# SCH_Nucleo____2022-11-04.net
KiCad netlist of a schematic drawn in EasyEDA
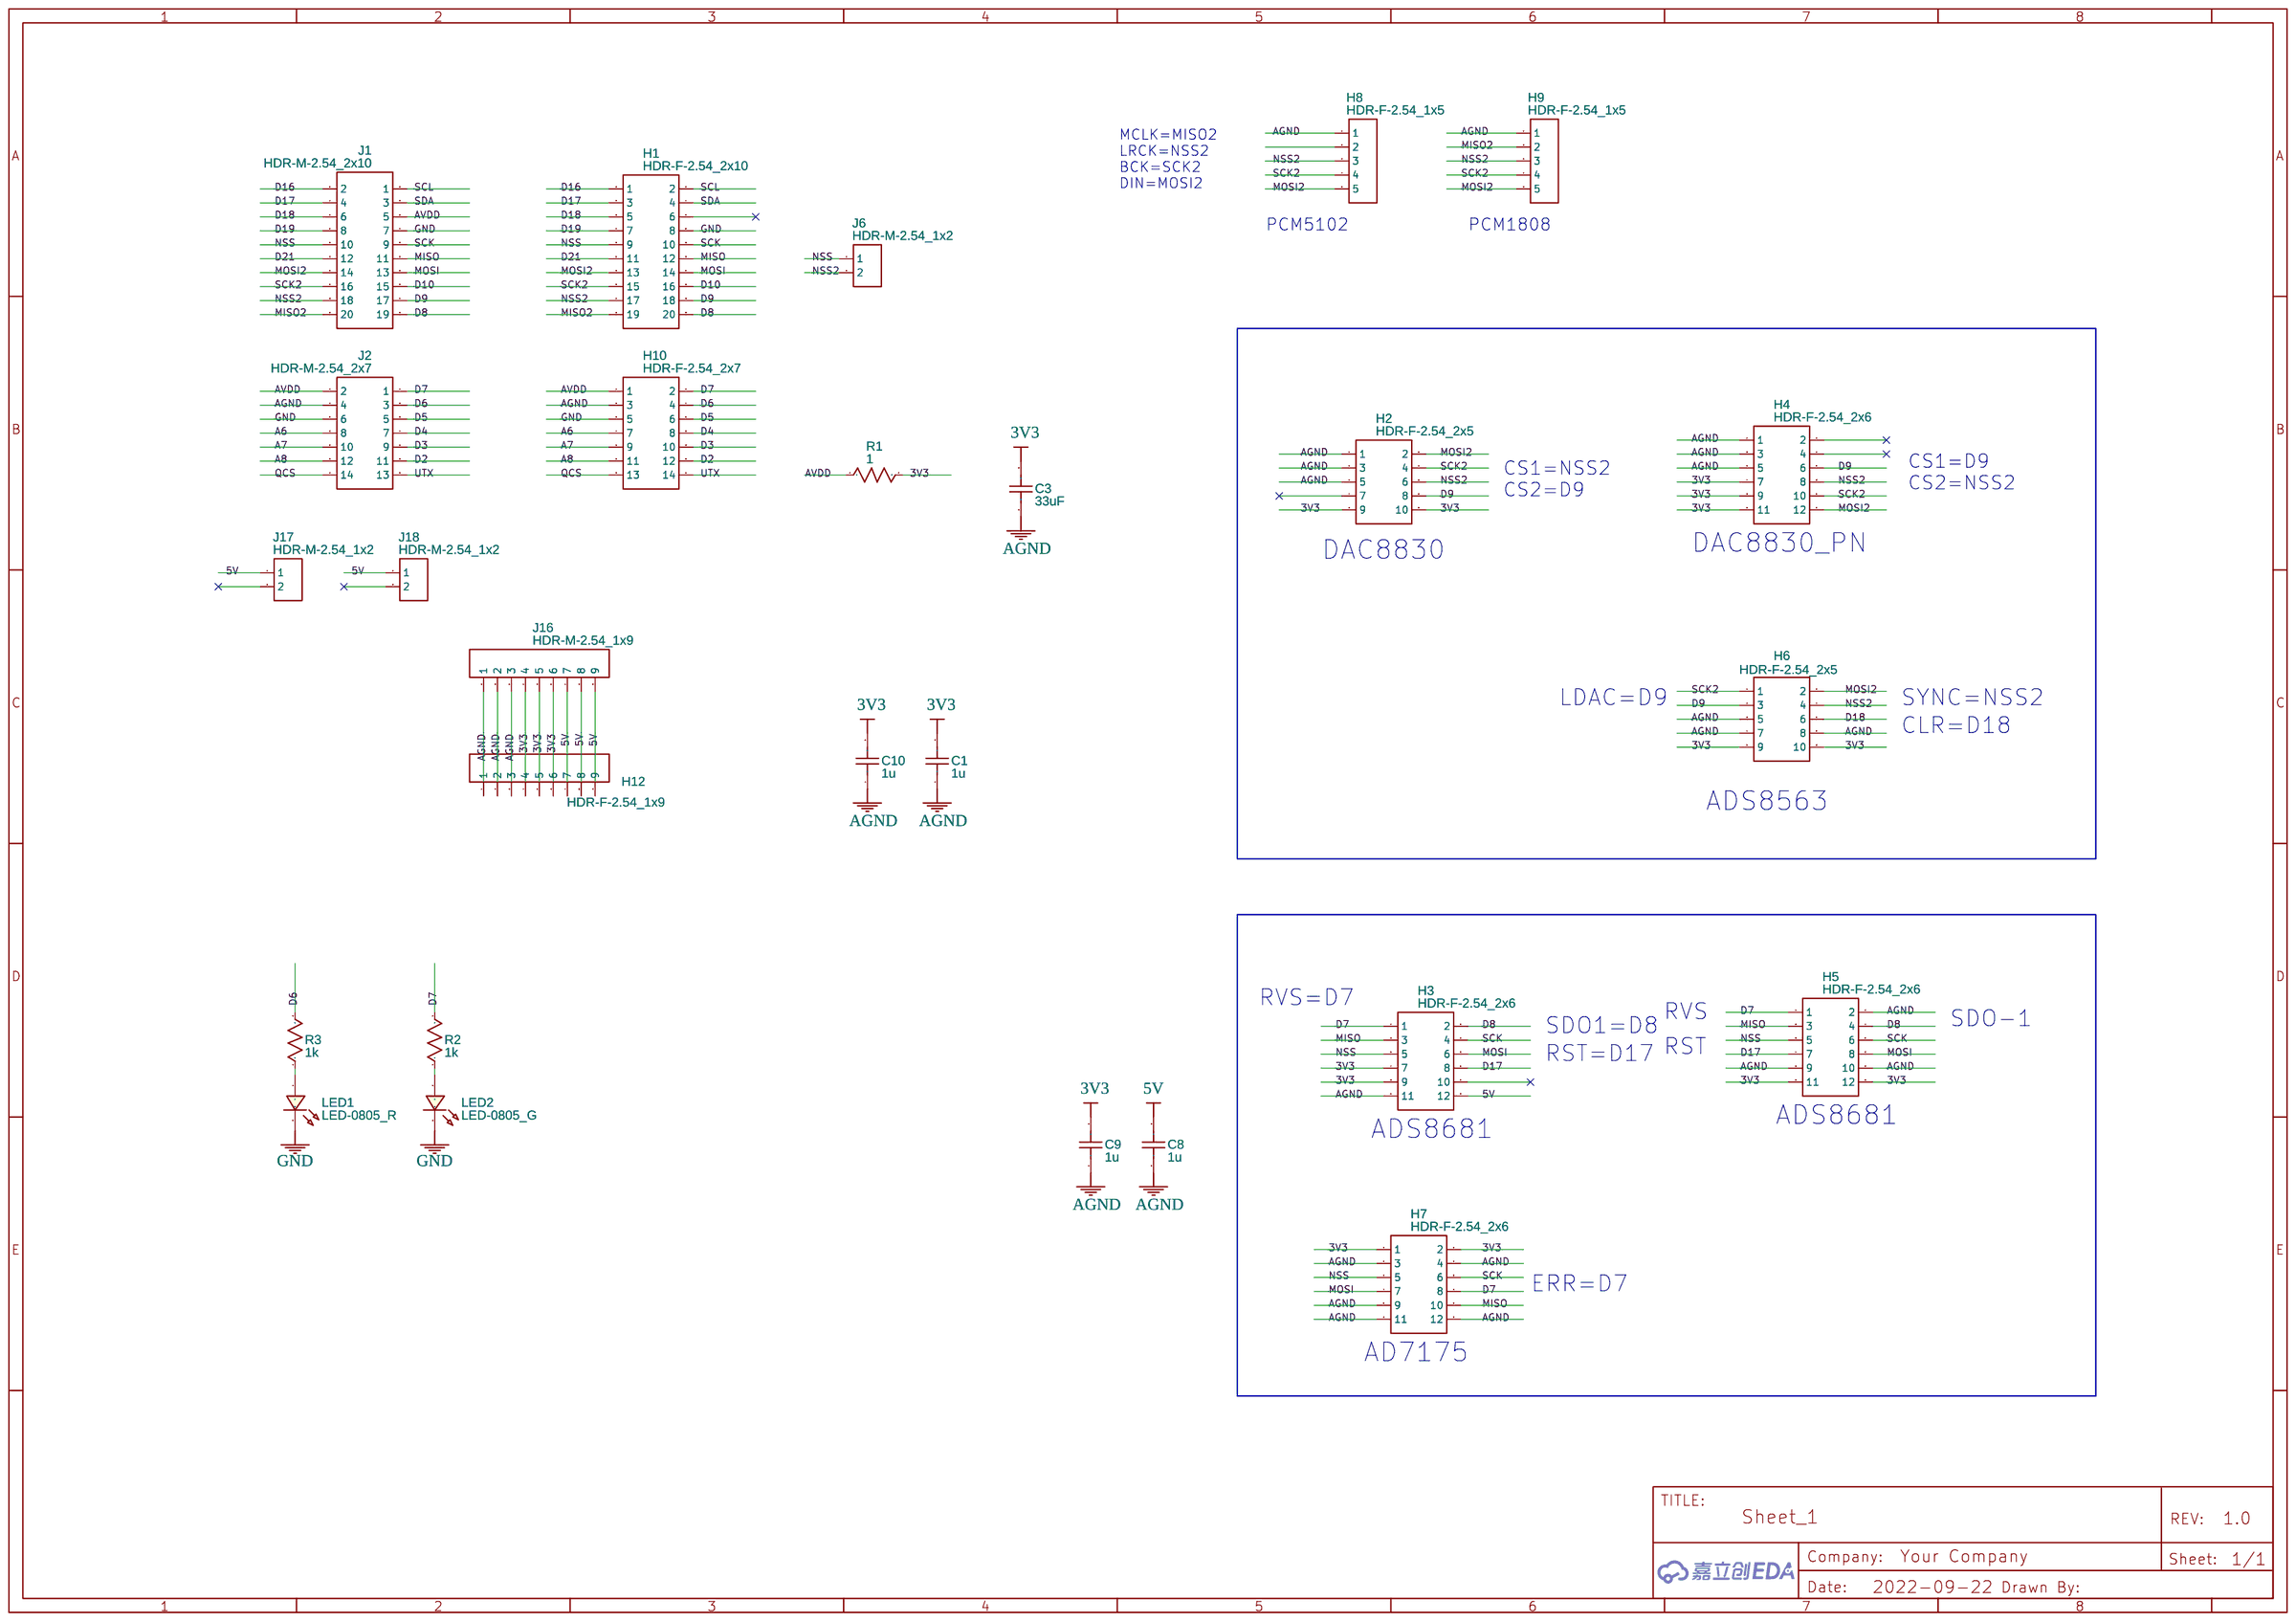
[diagram p0: 连接器]
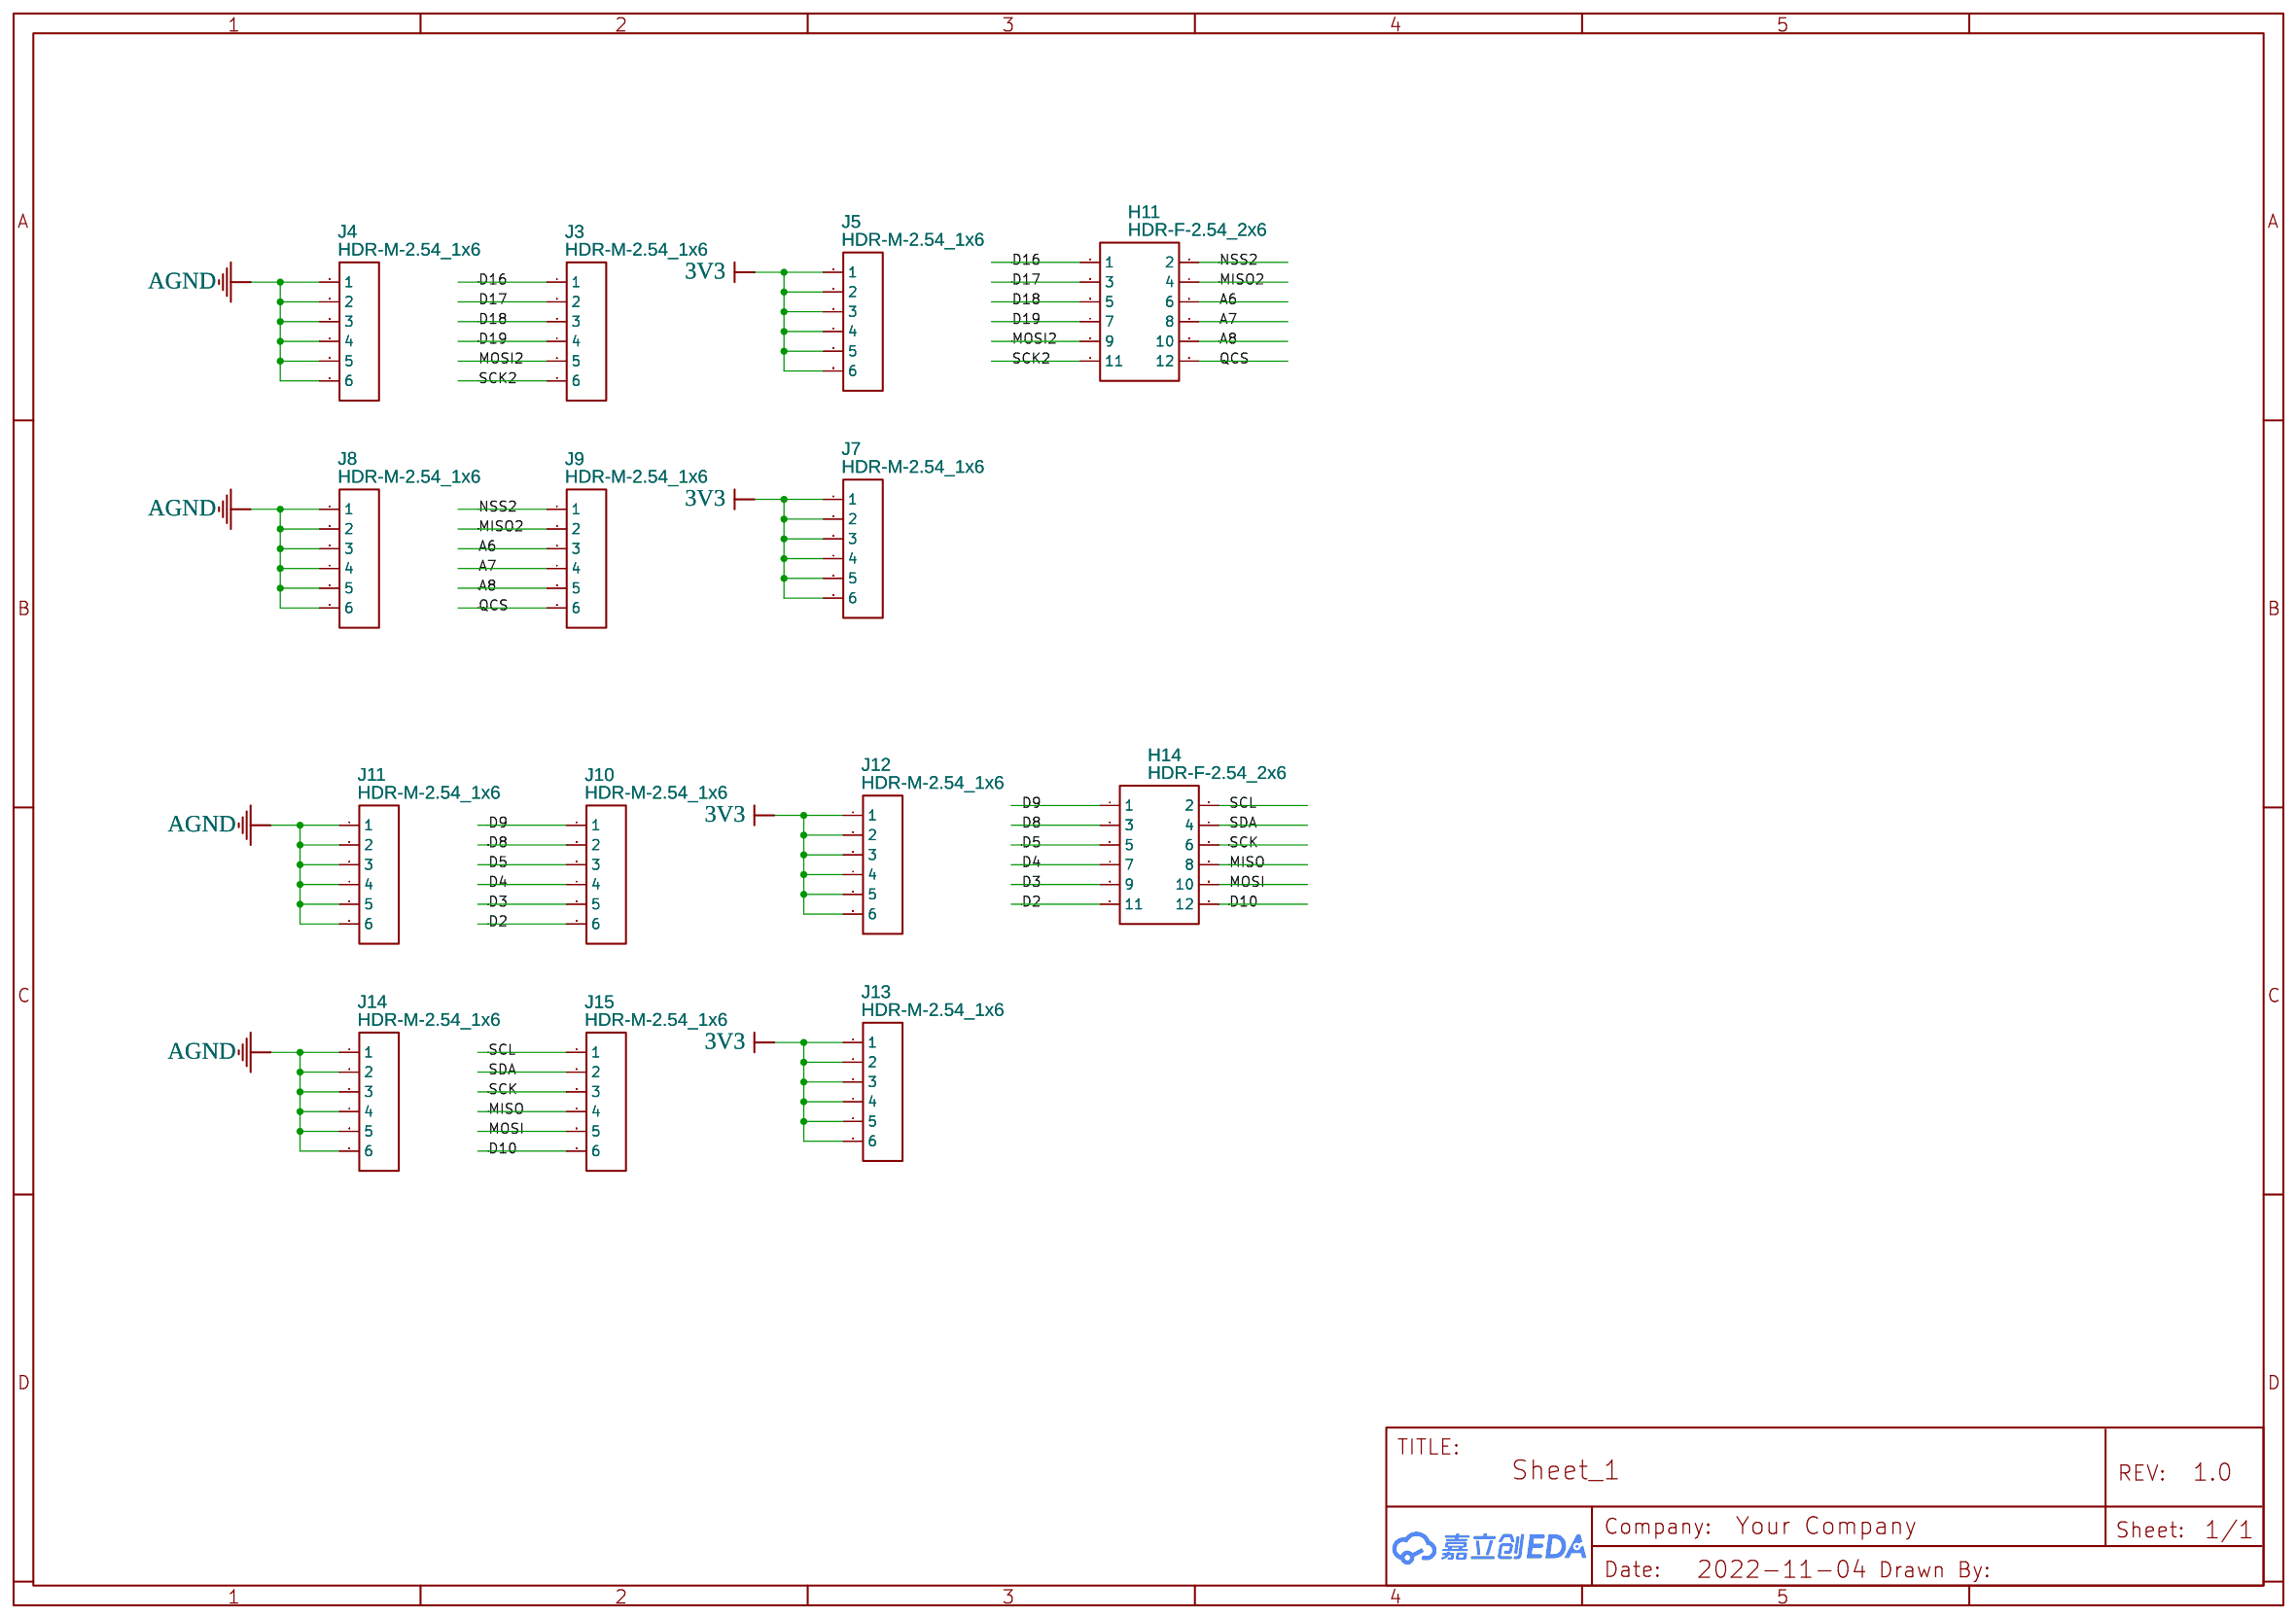
[diagram p1: 连接器2]

(export (version "E")
  (design (tool "Eeschema 10.0.6"))
  (components
    (comp (ref "C1")
      (value "1u")
      (fields
        (field (name "BOM_Manufacturer Part") "0805B105M500NT")
        (field (name "BOM_Supplier Part") "C2913555")
      )
      (libsource (lib "") (part "C_0805_US"))
    )
    (comp (ref "C3")
      (value "33uF")
      (fields
        (field (name "BOM_Manufacturer Part") "C3225X5R0J336MT0A0N")
        (field (name "BOM_Supplier Part") "C695362")
      )
      (libsource (lib "") (part "C3225X5R0J336MT0A0N"))
    )
    (comp (ref "C8")
      (value "1u")
      (fields
        (field (name "BOM_Manufacturer Part") "0805B105M500NT")
        (field (name "BOM_Supplier Part") "C2913555")
      )
      (libsource (lib "") (part "C_0805_US"))
    )
    (comp (ref "C9")
      (value "1u")
      (fields
        (field (name "BOM_Manufacturer Part") "0805B105M500NT")
        (field (name "BOM_Supplier Part") "C2913555")
      )
      (libsource (lib "") (part "C_0805_US"))
    )
    (comp (ref "C10")
      (value "1u")
      (fields
        (field (name "BOM_Manufacturer Part") "0805B105M500NT")
        (field (name "BOM_Supplier Part") "C2913555")
      )
      (libsource (lib "") (part "C_0805_US"))
    )
    (comp (ref "H1")
      (value "HDR-F-2.54_2x10")
      (fields (field (name "BOM_Supplier Part") "C30867"))
      (libsource (lib "") (part "HDR-F-2.54_2x10"))
    )
    (comp (ref "H2")
      (value "HDR-F-2.54_2x5")
      (fields (field (name "BOM_Supplier Part") "C30419"))
      (libsource (lib "") (part "HDR-F-2.54_2x5"))
    )
    (comp (ref "H3")
      (value "HDR-F-2.54_2x6")
      (fields (field (name "BOM_Supplier Part") "C36191"))
      (libsource (lib "") (part "HDR-F-2.54_2x6"))
    )
    (comp (ref "H4")
      (value "HDR-F-2.54_2x6")
      (fields (field (name "BOM_Supplier Part") "C36191"))
      (libsource (lib "") (part "HDR-F-2.54_2x6"))
    )
    (comp (ref "H5")
      (value "HDR-F-2.54_2x6")
      (fields (field (name "BOM_Supplier Part") "C36191"))
      (libsource (lib "") (part "HDR-F-2.54_2x6"))
    )
    (comp (ref "H6")
      (value "HDR-F-2.54_2x5")
      (fields (field (name "BOM_Supplier Part") "C30419"))
      (libsource (lib "") (part "HDR-F-2.54_2x5"))
    )
    (comp (ref "H7")
      (value "HDR-F-2.54_2x6")
      (fields (field (name "BOM_Supplier Part") "C36191"))
      (libsource (lib "") (part "HDR-F-2.54_2x6"))
    )
    (comp (ref "H8")
      (value "HDR-F-2.54_1x5")
      (fields (field (name "BOM_Supplier Part") "C50950"))
      (libsource (lib "") (part "HDR-F-2.54_1x5"))
    )
    (comp (ref "H9")
      (value "HDR-F-2.54_1x5")
      (fields (field (name "BOM_Supplier Part") "C50950"))
      (libsource (lib "") (part "HDR-F-2.54_1x5"))
    )
    (comp (ref "H10")
      (value "HDR-F-2.54_2x7")
      (fields (field (name "BOM_Supplier Part") "C38844"))
      (libsource (lib "") (part "HDR-F-2.54_2x7"))
    )
    (comp (ref "H12")
      (value "HDR-F-2.54_1x9")
      (fields (field (name "BOM_Supplier Part") "C124417"))
      (libsource (lib "") (part "HDR-F-2.54_1x9"))
    )
    (comp (ref "J1")
      (value "HDR-M-2.54_2x10")
      (fields (field (name "BOM_Supplier Part") "C124359"))
      (libsource (lib "") (part "HDR-M-2.54_2x10"))
    )
    (comp (ref "J2")
      (value "HDR-M-2.54_2x7")
      (fields (field (name "BOM_Supplier Part") "C71397"))
      (libsource (lib "") (part "HDR-M-2.54_2x7"))
    )
    (comp (ref "J6")
      (value "HDR-M-2.54_1x2")
      (fields (field (name "BOM_Supplier Part") "C124375"))
      (libsource (lib "") (part "HDR-M-2.54_1x2"))
    )
    (comp (ref "J16")
      (value "HDR-M-2.54_1x9")
      (fields (field (name "BOM_Supplier Part") "C225484"))
      (libsource (lib "") (part "HDR-M-2.54_1x9"))
    )
    (comp (ref "J17")
      (value "HDR-M-2.54_1x2")
      (fields (field (name "BOM_Supplier Part") "C124375"))
      (libsource (lib "") (part "HDR-M-2.54_1x2"))
    )
    (comp (ref "J18")
      (value "HDR-M-2.54_1x2")
      (fields (field (name "BOM_Supplier Part") "C124375"))
      (libsource (lib "") (part "HDR-M-2.54_1x2"))
    )
    (comp (ref "LED1")
      (value "LED-0805_R")
      (fields
        (field (name "BOM_Manufacturer Part") "17-21SURC/S530-A3/TR8")
        (field (name "BOM_Supplier Part") "C72037")
      )
      (libsource (lib "") (part "LED-0805_R"))
    )
    (comp (ref "LED2")
      (value "LED-0805_G")
      (fields (field (name "BOM_Manufacturer Part") "NCD0805G1") (field (name "BOM_Supplier Part") "C84260"))
      (libsource (lib "") (part "LED-0805_G"))
    )
    (comp (ref "R1") (value "1") (libsource (lib "") (part "R_0805_US_1")))
    (comp (ref "R2")
      (value "1k")
      (fields
        (field (name "BOM_Manufacturer Part") "TC0525F1001T5E")
        (field (name "BOM_Supplier Part") "C75781")
      )
      (libsource (lib "") (part "R_0805_US"))
    )
    (comp (ref "R3")
      (value "1k")
      (fields
        (field (name "BOM_Manufacturer Part") "TC0525F1001T5E")
        (field (name "BOM_Supplier Part") "C75781")
      )
      (libsource (lib "") (part "R_0805_US"))
    )
    (comp (ref "H11")
      (value "HDR-F-2.54_2x6")
      (fields (field (name "BOM_Supplier Part") "C36191"))
      (libsource (lib "") (part "HDR-F-2.54_2x6"))
    )
    (comp (ref "H14")
      (value "HDR-F-2.54_2x6")
      (fields (field (name "BOM_Supplier Part") "C36191"))
      (libsource (lib "") (part "HDR-F-2.54_2x6"))
    )
    (comp (ref "J3")
      (value "HDR-M-2.54_1x6")
      (fields (field (name "BOM_Supplier Part") "C190819"))
      (libsource (lib "") (part "HDR-M-2.54_1x6"))
    )
    (comp (ref "J4")
      (value "HDR-M-2.54_1x6")
      (fields (field (name "BOM_Supplier Part") "C190819"))
      (libsource (lib "") (part "HDR-M-2.54_1x6"))
    )
    (comp (ref "J5")
      (value "HDR-M-2.54_1x6")
      (fields (field (name "BOM_Supplier Part") "C190819"))
      (libsource (lib "") (part "HDR-M-2.54_1x6"))
    )
    (comp (ref "J7")
      (value "HDR-M-2.54_1x6")
      (fields (field (name "BOM_Supplier Part") "C190819"))
      (libsource (lib "") (part "HDR-M-2.54_1x6"))
    )
    (comp (ref "J8")
      (value "HDR-M-2.54_1x6")
      (fields (field (name "BOM_Supplier Part") "C190819"))
      (libsource (lib "") (part "HDR-M-2.54_1x6"))
    )
    (comp (ref "J9")
      (value "HDR-M-2.54_1x6")
      (fields (field (name "BOM_Supplier Part") "C190819"))
      (libsource (lib "") (part "HDR-M-2.54_1x6"))
    )
    (comp (ref "J10")
      (value "HDR-M-2.54_1x6")
      (fields (field (name "BOM_Supplier Part") "C190819"))
      (libsource (lib "") (part "HDR-M-2.54_1x6"))
    )
    (comp (ref "J11")
      (value "HDR-M-2.54_1x6")
      (fields (field (name "BOM_Supplier Part") "C190819"))
      (libsource (lib "") (part "HDR-M-2.54_1x6"))
    )
    (comp (ref "J12")
      (value "HDR-M-2.54_1x6")
      (fields (field (name "BOM_Supplier Part") "C190819"))
      (libsource (lib "") (part "HDR-M-2.54_1x6"))
    )
    (comp (ref "J13")
      (value "HDR-M-2.54_1x6")
      (fields (field (name "BOM_Supplier Part") "C190819"))
      (libsource (lib "") (part "HDR-M-2.54_1x6"))
    )
    (comp (ref "J14")
      (value "HDR-M-2.54_1x6")
      (fields (field (name "BOM_Supplier Part") "C190819"))
      (libsource (lib "") (part "HDR-M-2.54_1x6"))
    )
    (comp (ref "J15")
      (value "HDR-M-2.54_1x6")
      (fields (field (name "BOM_Supplier Part") "C190819"))
      (libsource (lib "") (part "HDR-M-2.54_1x6"))
    )
  )
  (nets
    (net (code "1") (name "3V3") (class "Default")
      (node (ref "C1") (pin "2") (pinfunction "2_2") (pintype "unspecified"))
      (node (ref "C10") (pin "2") (pinfunction "2_2") (pintype "unspecified"))
      (node (ref "C3") (pin "2") (pinfunction "2_2") (pintype "unspecified"))
      (node (ref "C9") (pin "2") (pinfunction "2_2") (pintype "unspecified"))
      (node (ref "H12") (pin "4") (pinfunction "4_4") (pintype "unspecified"))
      (node (ref "H12") (pin "5") (pinfunction "5_5") (pintype "unspecified"))
      (node (ref "H12") (pin "6") (pinfunction "6_6") (pintype "unspecified"))
      (node (ref "H2") (pin "10") (pinfunction "10_10") (pintype "unspecified"))
      (node (ref "H2") (pin "9") (pinfunction "9_9") (pintype "unspecified"))
      (node (ref "H3") (pin "7") (pinfunction "7_7") (pintype "input"))
      (node (ref "H3") (pin "9") (pinfunction "9_9") (pintype "input"))
      (node (ref "H4") (pin "11") (pinfunction "11_11") (pintype "input"))
      (node (ref "H4") (pin "7") (pinfunction "7_7") (pintype "input"))
      (node (ref "H4") (pin "9") (pinfunction "9_9") (pintype "input"))
      (node (ref "H5") (pin "11") (pinfunction "11_11") (pintype "input"))
      (node (ref "H5") (pin "12") (pinfunction "12_12") (pintype "input"))
      (node (ref "H6") (pin "10") (pinfunction "10_10") (pintype "unspecified"))
      (node (ref "H6") (pin "9") (pinfunction "9_9") (pintype "unspecified"))
      (node (ref "H7") (pin "1") (pinfunction "1_1") (pintype "input"))
      (node (ref "H7") (pin "2") (pinfunction "2_2") (pintype "input"))
      (node (ref "J12") (pin "1") (pinfunction "1_1") (pintype "input"))
      (node (ref "J12") (pin "2") (pinfunction "2_2") (pintype "input"))
      (node (ref "J12") (pin "3") (pinfunction "3_3") (pintype "input"))
      (node (ref "J12") (pin "4") (pinfunction "4_4") (pintype "input"))
      (node (ref "J12") (pin "5") (pinfunction "5_5") (pintype "input"))
      (node (ref "J12") (pin "6") (pinfunction "6_6") (pintype "input"))
      (node (ref "J13") (pin "1") (pinfunction "1_1") (pintype "input"))
      (node (ref "J13") (pin "2") (pinfunction "2_2") (pintype "input"))
      (node (ref "J13") (pin "3") (pinfunction "3_3") (pintype "input"))
      (node (ref "J13") (pin "4") (pinfunction "4_4") (pintype "input"))
      (node (ref "J13") (pin "5") (pinfunction "5_5") (pintype "input"))
      (node (ref "J13") (pin "6") (pinfunction "6_6") (pintype "input"))
      (node (ref "J16") (pin "4") (pinfunction "4_4") (pintype "unspecified"))
      (node (ref "J16") (pin "5") (pinfunction "5_5") (pintype "unspecified"))
      (node (ref "J16") (pin "6") (pinfunction "6_6") (pintype "unspecified"))
      (node (ref "J5") (pin "1") (pinfunction "1_1") (pintype "input"))
      (node (ref "J5") (pin "2") (pinfunction "2_2") (pintype "input"))
      (node (ref "J5") (pin "3") (pinfunction "3_3") (pintype "input"))
      (node (ref "J5") (pin "4") (pinfunction "4_4") (pintype "input"))
      (node (ref "J5") (pin "5") (pinfunction "5_5") (pintype "input"))
      (node (ref "J5") (pin "6") (pinfunction "6_6") (pintype "input"))
      (node (ref "J7") (pin "1") (pinfunction "1_1") (pintype "input"))
      (node (ref "J7") (pin "2") (pinfunction "2_2") (pintype "input"))
      (node (ref "J7") (pin "3") (pinfunction "3_3") (pintype "input"))
      (node (ref "J7") (pin "4") (pinfunction "4_4") (pintype "input"))
      (node (ref "J7") (pin "5") (pinfunction "5_5") (pintype "input"))
      (node (ref "J7") (pin "6") (pinfunction "6_6") (pintype "input"))
      (node (ref "R1") (pin "2") (pinfunction "2_2") (pintype "unspecified"))
    )
    (net (code "2") (name "5V") (class "Default")
      (node (ref "C8") (pin "2") (pinfunction "2_2") (pintype "unspecified"))
      (node (ref "H12") (pin "7") (pinfunction "7_7") (pintype "unspecified"))
      (node (ref "H12") (pin "8") (pinfunction "8_8") (pintype "unspecified"))
      (node (ref "H12") (pin "9") (pinfunction "9_9") (pintype "unspecified"))
      (node (ref "H3") (pin "12") (pinfunction "12_12") (pintype "input"))
      (node (ref "J16") (pin "7") (pinfunction "7_7") (pintype "unspecified"))
      (node (ref "J16") (pin "8") (pinfunction "8_8") (pintype "unspecified"))
      (node (ref "J16") (pin "9") (pinfunction "9_9") (pintype "unspecified"))
      (node (ref "J17") (pin "1") (pinfunction "1_1") (pintype "unspecified"))
      (node (ref "J18") (pin "1") (pinfunction "1_1") (pintype "unspecified"))
    )
    (net (code "3") (name "A6") (class "Default")
      (node (ref "H10") (pin "7") (pinfunction "7_7") (pintype "input"))
      (node (ref "H11") (pin "6") (pinfunction "6_6") (pintype "input"))
      (node (ref "J2") (pin "8") (pinfunction "8_8") (pintype "input"))
      (node (ref "J9") (pin "3") (pinfunction "3_3") (pintype "input"))
    )
    (net (code "4") (name "A7") (class "Default")
      (node (ref "H10") (pin "9") (pinfunction "9_9") (pintype "input"))
      (node (ref "H11") (pin "8") (pinfunction "8_8") (pintype "input"))
      (node (ref "J2") (pin "10") (pinfunction "10_10") (pintype "input"))
      (node (ref "J9") (pin "4") (pinfunction "4_4") (pintype "input"))
    )
    (net (code "5") (name "A8") (class "Default")
      (node (ref "H10") (pin "11") (pinfunction "11_11") (pintype "input"))
      (node (ref "H11") (pin "10") (pinfunction "10_10") (pintype "input"))
      (node (ref "J2") (pin "12") (pinfunction "12_12") (pintype "input"))
      (node (ref "J9") (pin "5") (pinfunction "5_5") (pintype "input"))
    )
    (net (code "6") (name "AGND") (class "Default")
      (node (ref "C1") (pin "1") (pinfunction "1_1") (pintype "unspecified"))
      (node (ref "C10") (pin "1") (pinfunction "1_1") (pintype "unspecified"))
      (node (ref "C3") (pin "1") (pinfunction "1_1") (pintype "unspecified"))
      (node (ref "C8") (pin "1") (pinfunction "1_1") (pintype "unspecified"))
      (node (ref "C9") (pin "1") (pinfunction "1_1") (pintype "unspecified"))
      (node (ref "H10") (pin "3") (pinfunction "3_3") (pintype "input"))
      (node (ref "H12") (pin "1") (pinfunction "1_1") (pintype "unspecified"))
      (node (ref "H12") (pin "2") (pinfunction "2_2") (pintype "unspecified"))
      (node (ref "H12") (pin "3") (pinfunction "3_3") (pintype "unspecified"))
      (node (ref "H2") (pin "1") (pinfunction "1_1") (pintype "unspecified"))
      (node (ref "H2") (pin "3") (pinfunction "3_3") (pintype "unspecified"))
      (node (ref "H2") (pin "5") (pinfunction "5_5") (pintype "unspecified"))
      (node (ref "H3") (pin "11") (pinfunction "11_11") (pintype "input"))
      (node (ref "H4") (pin "1") (pinfunction "1_1") (pintype "input"))
      (node (ref "H4") (pin "3") (pinfunction "3_3") (pintype "input"))
      (node (ref "H4") (pin "5") (pinfunction "5_5") (pintype "input"))
      (node (ref "H5") (pin "10") (pinfunction "10_10") (pintype "input"))
      (node (ref "H5") (pin "2") (pinfunction "2_2") (pintype "input"))
      (node (ref "H5") (pin "9") (pinfunction "9_9") (pintype "input"))
      (node (ref "H6") (pin "5") (pinfunction "5_5") (pintype "unspecified"))
      (node (ref "H6") (pin "7") (pinfunction "7_7") (pintype "unspecified"))
      (node (ref "H6") (pin "8") (pinfunction "8_8") (pintype "unspecified"))
      (node (ref "H7") (pin "11") (pinfunction "11_11") (pintype "input"))
      (node (ref "H7") (pin "12") (pinfunction "12_12") (pintype "input"))
      (node (ref "H7") (pin "3") (pinfunction "3_3") (pintype "input"))
      (node (ref "H7") (pin "4") (pinfunction "4_4") (pintype "input"))
      (node (ref "H7") (pin "9") (pinfunction "9_9") (pintype "input"))
      (node (ref "H8") (pin "1") (pinfunction "1_1") (pintype "unspecified"))
      (node (ref "H9") (pin "1") (pinfunction "1_1") (pintype "unspecified"))
      (node (ref "J11") (pin "1") (pinfunction "1_1") (pintype "input"))
      (node (ref "J11") (pin "2") (pinfunction "2_2") (pintype "input"))
      (node (ref "J11") (pin "3") (pinfunction "3_3") (pintype "input"))
      (node (ref "J11") (pin "4") (pinfunction "4_4") (pintype "input"))
      (node (ref "J11") (pin "5") (pinfunction "5_5") (pintype "input"))
      (node (ref "J11") (pin "6") (pinfunction "6_6") (pintype "input"))
      (node (ref "J14") (pin "1") (pinfunction "1_1") (pintype "input"))
      (node (ref "J14") (pin "2") (pinfunction "2_2") (pintype "input"))
      (node (ref "J14") (pin "3") (pinfunction "3_3") (pintype "input"))
      (node (ref "J14") (pin "4") (pinfunction "4_4") (pintype "input"))
      (node (ref "J14") (pin "5") (pinfunction "5_5") (pintype "input"))
      (node (ref "J14") (pin "6") (pinfunction "6_6") (pintype "input"))
      (node (ref "J16") (pin "1") (pinfunction "1_1") (pintype "unspecified"))
      (node (ref "J16") (pin "2") (pinfunction "2_2") (pintype "unspecified"))
      (node (ref "J16") (pin "3") (pinfunction "3_3") (pintype "unspecified"))
      (node (ref "J2") (pin "4") (pinfunction "4_4") (pintype "input"))
      (node (ref "J4") (pin "1") (pinfunction "1_1") (pintype "input"))
      (node (ref "J4") (pin "2") (pinfunction "2_2") (pintype "input"))
      (node (ref "J4") (pin "3") (pinfunction "3_3") (pintype "input"))
      (node (ref "J4") (pin "4") (pinfunction "4_4") (pintype "input"))
      (node (ref "J4") (pin "5") (pinfunction "5_5") (pintype "input"))
      (node (ref "J4") (pin "6") (pinfunction "6_6") (pintype "input"))
      (node (ref "J8") (pin "1") (pinfunction "1_1") (pintype "input"))
      (node (ref "J8") (pin "2") (pinfunction "2_2") (pintype "input"))
      (node (ref "J8") (pin "3") (pinfunction "3_3") (pintype "input"))
      (node (ref "J8") (pin "4") (pinfunction "4_4") (pintype "input"))
      (node (ref "J8") (pin "5") (pinfunction "5_5") (pintype "input"))
      (node (ref "J8") (pin "6") (pinfunction "6_6") (pintype "input"))
    )
    (net (code "7") (name "AVDD") (class "Default")
      (node (ref "H10") (pin "1") (pinfunction "1_1") (pintype "input"))
      (node (ref "J1") (pin "5") (pinfunction "5_5") (pintype "unspecified"))
      (node (ref "J2") (pin "2") (pinfunction "2_2") (pintype "input"))
      (node (ref "R1") (pin "1") (pinfunction "1_1") (pintype "unspecified"))
    )
    (net (code "8") (name "D2") (class "Default")
      (node (ref "H10") (pin "12") (pinfunction "12_12") (pintype "input"))
      (node (ref "H14") (pin "11") (pinfunction "11_11") (pintype "input"))
      (node (ref "J10") (pin "6") (pinfunction "6_6") (pintype "input"))
      (node (ref "J2") (pin "11") (pinfunction "11_11") (pintype "input"))
    )
    (net (code "9") (name "D3") (class "Default")
      (node (ref "H10") (pin "10") (pinfunction "10_10") (pintype "input"))
      (node (ref "H14") (pin "9") (pinfunction "9_9") (pintype "input"))
      (node (ref "J10") (pin "5") (pinfunction "5_5") (pintype "input"))
      (node (ref "J2") (pin "9") (pinfunction "9_9") (pintype "input"))
    )
    (net (code "10") (name "D4") (class "Default")
      (node (ref "H10") (pin "8") (pinfunction "8_8") (pintype "input"))
      (node (ref "H14") (pin "7") (pinfunction "7_7") (pintype "input"))
      (node (ref "J10") (pin "4") (pinfunction "4_4") (pintype "input"))
      (node (ref "J2") (pin "7") (pinfunction "7_7") (pintype "input"))
    )
    (net (code "11") (name "D5") (class "Default")
      (node (ref "H10") (pin "6") (pinfunction "6_6") (pintype "input"))
      (node (ref "H14") (pin "5") (pinfunction "5_5") (pintype "input"))
      (node (ref "J10") (pin "3") (pinfunction "3_3") (pintype "input"))
      (node (ref "J2") (pin "5") (pinfunction "5_5") (pintype "input"))
    )
    (net (code "12") (name "D6") (class "Default")
      (node (ref "H10") (pin "4") (pinfunction "4_4") (pintype "input"))
      (node (ref "J2") (pin "3") (pinfunction "3_3") (pintype "input"))
      (node (ref "R3") (pin "2") (pinfunction "2_2") (pintype "unspecified"))
    )
    (net (code "13") (name "D7") (class "Default")
      (node (ref "H10") (pin "2") (pinfunction "2_2") (pintype "input"))
      (node (ref "H3") (pin "1") (pinfunction "1_1") (pintype "input"))
      (node (ref "H5") (pin "1") (pinfunction "1_1") (pintype "input"))
      (node (ref "H7") (pin "8") (pinfunction "8_8") (pintype "input"))
      (node (ref "J2") (pin "1") (pinfunction "1_1") (pintype "input"))
      (node (ref "R2") (pin "2") (pinfunction "2_2") (pintype "unspecified"))
    )
    (net (code "14") (name "D8") (class "Default")
      (node (ref "H1") (pin "20") (pinfunction "20_20") (pintype "input"))
      (node (ref "H14") (pin "3") (pinfunction "3_3") (pintype "input"))
      (node (ref "H3") (pin "2") (pinfunction "2_2") (pintype "input"))
      (node (ref "H5") (pin "4") (pinfunction "4_4") (pintype "input"))
      (node (ref "J1") (pin "19") (pinfunction "19_19") (pintype "unspecified"))
      (node (ref "J10") (pin "2") (pinfunction "2_2") (pintype "input"))
    )
    (net (code "15") (name "D9") (class "Default")
      (node (ref "H1") (pin "18") (pinfunction "18_18") (pintype "input"))
      (node (ref "H14") (pin "1") (pinfunction "1_1") (pintype "input"))
      (node (ref "H2") (pin "8") (pinfunction "8_8") (pintype "unspecified"))
      (node (ref "H4") (pin "6") (pinfunction "6_6") (pintype "input"))
      (node (ref "H6") (pin "3") (pinfunction "3_3") (pintype "unspecified"))
      (node (ref "J1") (pin "17") (pinfunction "17_17") (pintype "unspecified"))
      (node (ref "J10") (pin "1") (pinfunction "1_1") (pintype "input"))
    )
    (net (code "16") (name "D10") (class "Default")
      (node (ref "H1") (pin "16") (pinfunction "16_16") (pintype "input"))
      (node (ref "H14") (pin "12") (pinfunction "12_12") (pintype "input"))
      (node (ref "J1") (pin "15") (pinfunction "15_15") (pintype "unspecified"))
      (node (ref "J15") (pin "6") (pinfunction "6_6") (pintype "input"))
    )
    (net (code "17") (name "D16") (class "Default")
      (node (ref "H1") (pin "1") (pinfunction "1_1") (pintype "input"))
      (node (ref "H11") (pin "1") (pinfunction "1_1") (pintype "input"))
      (node (ref "J1") (pin "2") (pinfunction "2_2") (pintype "unspecified"))
      (node (ref "J3") (pin "1") (pinfunction "1_1") (pintype "input"))
    )
    (net (code "18") (name "D17") (class "Default")
      (node (ref "H1") (pin "3") (pinfunction "3_3") (pintype "input"))
      (node (ref "H11") (pin "3") (pinfunction "3_3") (pintype "input"))
      (node (ref "H3") (pin "8") (pinfunction "8_8") (pintype "input"))
      (node (ref "H5") (pin "7") (pinfunction "7_7") (pintype "input"))
      (node (ref "J1") (pin "4") (pinfunction "4_4") (pintype "unspecified"))
      (node (ref "J3") (pin "2") (pinfunction "2_2") (pintype "input"))
    )
    (net (code "19") (name "D18") (class "Default")
      (node (ref "H1") (pin "5") (pinfunction "5_5") (pintype "input"))
      (node (ref "H11") (pin "5") (pinfunction "5_5") (pintype "input"))
      (node (ref "H6") (pin "6") (pinfunction "6_6") (pintype "unspecified"))
      (node (ref "J1") (pin "6") (pinfunction "6_6") (pintype "unspecified"))
      (node (ref "J3") (pin "3") (pinfunction "3_3") (pintype "input"))
    )
    (net (code "20") (name "D19") (class "Default")
      (node (ref "H1") (pin "7") (pinfunction "7_7") (pintype "input"))
      (node (ref "H11") (pin "7") (pinfunction "7_7") (pintype "input"))
      (node (ref "J1") (pin "8") (pinfunction "8_8") (pintype "unspecified"))
      (node (ref "J3") (pin "4") (pinfunction "4_4") (pintype "input"))
    )
    (net (code "21") (name "D21") (class "Default")
      (node (ref "H1") (pin "11") (pinfunction "11_11") (pintype "input"))
      (node (ref "J1") (pin "12") (pinfunction "12_12") (pintype "unspecified"))
    )
    (net (code "22") (name "GND") (class "Default")
      (node (ref "H1") (pin "8") (pinfunction "8_8") (pintype "input"))
      (node (ref "H10") (pin "5") (pinfunction "5_5") (pintype "input"))
      (node (ref "J1") (pin "7") (pinfunction "7_7") (pintype "unspecified"))
      (node (ref "J2") (pin "6") (pinfunction "6_6") (pintype "input"))
      (node (ref "LED1") (pin "2") (pinfunction "2_2") (pintype "unspecified"))
      (node (ref "LED2") (pin "2") (pinfunction "2_2") (pintype "unspecified"))
    )
    (net (code "23") (name "MISO") (class "Default")
      (node (ref "H1") (pin "12") (pinfunction "12_12") (pintype "input"))
      (node (ref "H14") (pin "8") (pinfunction "8_8") (pintype "input"))
      (node (ref "H3") (pin "3") (pinfunction "3_3") (pintype "input"))
      (node (ref "H5") (pin "3") (pinfunction "3_3") (pintype "input"))
      (node (ref "H7") (pin "10") (pinfunction "10_10") (pintype "input"))
      (node (ref "J1") (pin "11") (pinfunction "11_11") (pintype "unspecified"))
      (node (ref "J15") (pin "4") (pinfunction "4_4") (pintype "input"))
    )
    (net (code "24") (name "MISO2") (class "Default")
      (node (ref "H1") (pin "19") (pinfunction "19_19") (pintype "input"))
      (node (ref "H11") (pin "4") (pinfunction "4_4") (pintype "input"))
      (node (ref "H9") (pin "2") (pinfunction "2_2") (pintype "unspecified"))
      (node (ref "J1") (pin "20") (pinfunction "20_20") (pintype "unspecified"))
      (node (ref "J9") (pin "2") (pinfunction "2_2") (pintype "input"))
    )
    (net (code "25") (name "MOSI") (class "Default")
      (node (ref "H1") (pin "14") (pinfunction "14_14") (pintype "input"))
      (node (ref "H14") (pin "10") (pinfunction "10_10") (pintype "input"))
      (node (ref "H3") (pin "6") (pinfunction "6_6") (pintype "input"))
      (node (ref "H5") (pin "8") (pinfunction "8_8") (pintype "input"))
      (node (ref "H7") (pin "7") (pinfunction "7_7") (pintype "input"))
      (node (ref "J1") (pin "13") (pinfunction "13_13") (pintype "unspecified"))
      (node (ref "J15") (pin "5") (pinfunction "5_5") (pintype "input"))
    )
    (net (code "26") (name "MOSI2") (class "Default")
      (node (ref "H1") (pin "13") (pinfunction "13_13") (pintype "input"))
      (node (ref "H11") (pin "9") (pinfunction "9_9") (pintype "input"))
      (node (ref "H2") (pin "2") (pinfunction "2_2") (pintype "unspecified"))
      (node (ref "H4") (pin "12") (pinfunction "12_12") (pintype "input"))
      (node (ref "H6") (pin "2") (pinfunction "2_2") (pintype "unspecified"))
      (node (ref "H8") (pin "5") (pinfunction "5_5") (pintype "unspecified"))
      (node (ref "H9") (pin "5") (pinfunction "5_5") (pintype "unspecified"))
      (node (ref "J1") (pin "14") (pinfunction "14_14") (pintype "unspecified"))
      (node (ref "J3") (pin "5") (pinfunction "5_5") (pintype "input"))
    )
    (net (code "27") (name "NSS") (class "Default")
      (node (ref "H1") (pin "9") (pinfunction "9_9") (pintype "input"))
      (node (ref "H3") (pin "5") (pinfunction "5_5") (pintype "input"))
      (node (ref "H5") (pin "5") (pinfunction "5_5") (pintype "input"))
      (node (ref "H7") (pin "5") (pinfunction "5_5") (pintype "input"))
      (node (ref "J1") (pin "10") (pinfunction "10_10") (pintype "unspecified"))
      (node (ref "J6") (pin "1") (pinfunction "1_1") (pintype "unspecified"))
    )
    (net (code "28") (name "NSS2") (class "Default")
      (node (ref "H1") (pin "17") (pinfunction "17_17") (pintype "input"))
      (node (ref "H11") (pin "2") (pinfunction "2_2") (pintype "input"))
      (node (ref "H2") (pin "6") (pinfunction "6_6") (pintype "unspecified"))
      (node (ref "H4") (pin "8") (pinfunction "8_8") (pintype "input"))
      (node (ref "H6") (pin "4") (pinfunction "4_4") (pintype "unspecified"))
      (node (ref "H8") (pin "3") (pinfunction "3_3") (pintype "unspecified"))
      (node (ref "H9") (pin "3") (pinfunction "3_3") (pintype "unspecified"))
      (node (ref "J1") (pin "18") (pinfunction "18_18") (pintype "unspecified"))
      (node (ref "J6") (pin "2") (pinfunction "2_2") (pintype "unspecified"))
      (node (ref "J9") (pin "1") (pinfunction "1_1") (pintype "input"))
    )
    (net (code "29") (name "Net-(LED1-Pad1)") (class "Default")
      (node (ref "LED1") (pin "1") (pinfunction "1_1") (pintype "unspecified"))
      (node (ref "R3") (pin "1") (pinfunction "1_1") (pintype "unspecified"))
    )
    (net (code "30") (name "Net-(LED2-Pad1)") (class "Default")
      (node (ref "LED2") (pin "1") (pinfunction "1_1") (pintype "unspecified"))
      (node (ref "R2") (pin "1") (pinfunction "1_1") (pintype "unspecified"))
    )
    (net (code "31") (name "QCS") (class "Default")
      (node (ref "H10") (pin "13") (pinfunction "13_13") (pintype "input"))
      (node (ref "H11") (pin "12") (pinfunction "12_12") (pintype "input"))
      (node (ref "J2") (pin "14") (pinfunction "14_14") (pintype "input"))
      (node (ref "J9") (pin "6") (pinfunction "6_6") (pintype "input"))
    )
    (net (code "32") (name "SCK") (class "Default")
      (node (ref "H1") (pin "10") (pinfunction "10_10") (pintype "input"))
      (node (ref "H14") (pin "6") (pinfunction "6_6") (pintype "input"))
      (node (ref "H3") (pin "4") (pinfunction "4_4") (pintype "input"))
      (node (ref "H5") (pin "6") (pinfunction "6_6") (pintype "input"))
      (node (ref "H7") (pin "6") (pinfunction "6_6") (pintype "input"))
      (node (ref "J1") (pin "9") (pinfunction "9_9") (pintype "unspecified"))
      (node (ref "J15") (pin "3") (pinfunction "3_3") (pintype "input"))
    )
    (net (code "33") (name "SCK2") (class "Default")
      (node (ref "H1") (pin "15") (pinfunction "15_15") (pintype "input"))
      (node (ref "H11") (pin "11") (pinfunction "11_11") (pintype "input"))
      (node (ref "H2") (pin "4") (pinfunction "4_4") (pintype "unspecified"))
      (node (ref "H4") (pin "10") (pinfunction "10_10") (pintype "input"))
      (node (ref "H6") (pin "1") (pinfunction "1_1") (pintype "unspecified"))
      (node (ref "H8") (pin "4") (pinfunction "4_4") (pintype "unspecified"))
      (node (ref "H9") (pin "4") (pinfunction "4_4") (pintype "unspecified"))
      (node (ref "J1") (pin "16") (pinfunction "16_16") (pintype "unspecified"))
      (node (ref "J3") (pin "6") (pinfunction "6_6") (pintype "input"))
    )
    (net (code "34") (name "SCL") (class "Default")
      (node (ref "H1") (pin "2") (pinfunction "2_2") (pintype "input"))
      (node (ref "H14") (pin "2") (pinfunction "2_2") (pintype "input"))
      (node (ref "J1") (pin "1") (pinfunction "1_1") (pintype "unspecified"))
      (node (ref "J15") (pin "1") (pinfunction "1_1") (pintype "input"))
    )
    (net (code "35") (name "SDA") (class "Default")
      (node (ref "H1") (pin "4") (pinfunction "4_4") (pintype "input"))
      (node (ref "H14") (pin "4") (pinfunction "4_4") (pintype "input"))
      (node (ref "J1") (pin "3") (pinfunction "3_3") (pintype "unspecified"))
      (node (ref "J15") (pin "2") (pinfunction "2_2") (pintype "input"))
    )
    (net (code "36") (name "UTX") (class "Default")
      (node (ref "H10") (pin "14") (pinfunction "14_14") (pintype "input"))
      (node (ref "J2") (pin "13") (pinfunction "13_13") (pintype "input"))
    )
    (net (code "37") (name "unconnected-(H1-Pad6)") (class "Default")
      (node (ref "H1") (pin "6") (pinfunction "6_6") (pintype "input+no_connect"))
    )
    (net (code "38") (name "unconnected-(H2-Pad7)") (class "Default")
      (node (ref "H2") (pin "7") (pinfunction "7_7") (pintype "unspecified+no_connect"))
    )
    (net (code "39") (name "unconnected-(H3-Pad10)") (class "Default")
      (node (ref "H3") (pin "10") (pinfunction "10_10") (pintype "input+no_connect"))
    )
    (net (code "40") (name "unconnected-(H4-Pad2)") (class "Default")
      (node (ref "H4") (pin "2") (pinfunction "2_2") (pintype "input+no_connect"))
    )
    (net (code "41") (name "unconnected-(H4-Pad4)") (class "Default")
      (node (ref "H4") (pin "4") (pinfunction "4_4") (pintype "input+no_connect"))
    )
    (net (code "42") (name "unconnected-(H8-Pad2)") (class "Default")
      (node (ref "H8") (pin "2") (pinfunction "2_2") (pintype "unspecified"))
    )
    (net (code "43") (name "unconnected-(J17-Pad2)") (class "Default")
      (node (ref "J17") (pin "2") (pinfunction "2_2") (pintype "unspecified+no_connect"))
    )
    (net (code "44") (name "unconnected-(J18-Pad2)") (class "Default")
      (node (ref "J18") (pin "2") (pinfunction "2_2") (pintype "unspecified+no_connect"))
    )
  )
)
